# LPCB235_-_HEC5-8.net
KiCad netlist of a schematic drawn in Altium Designer
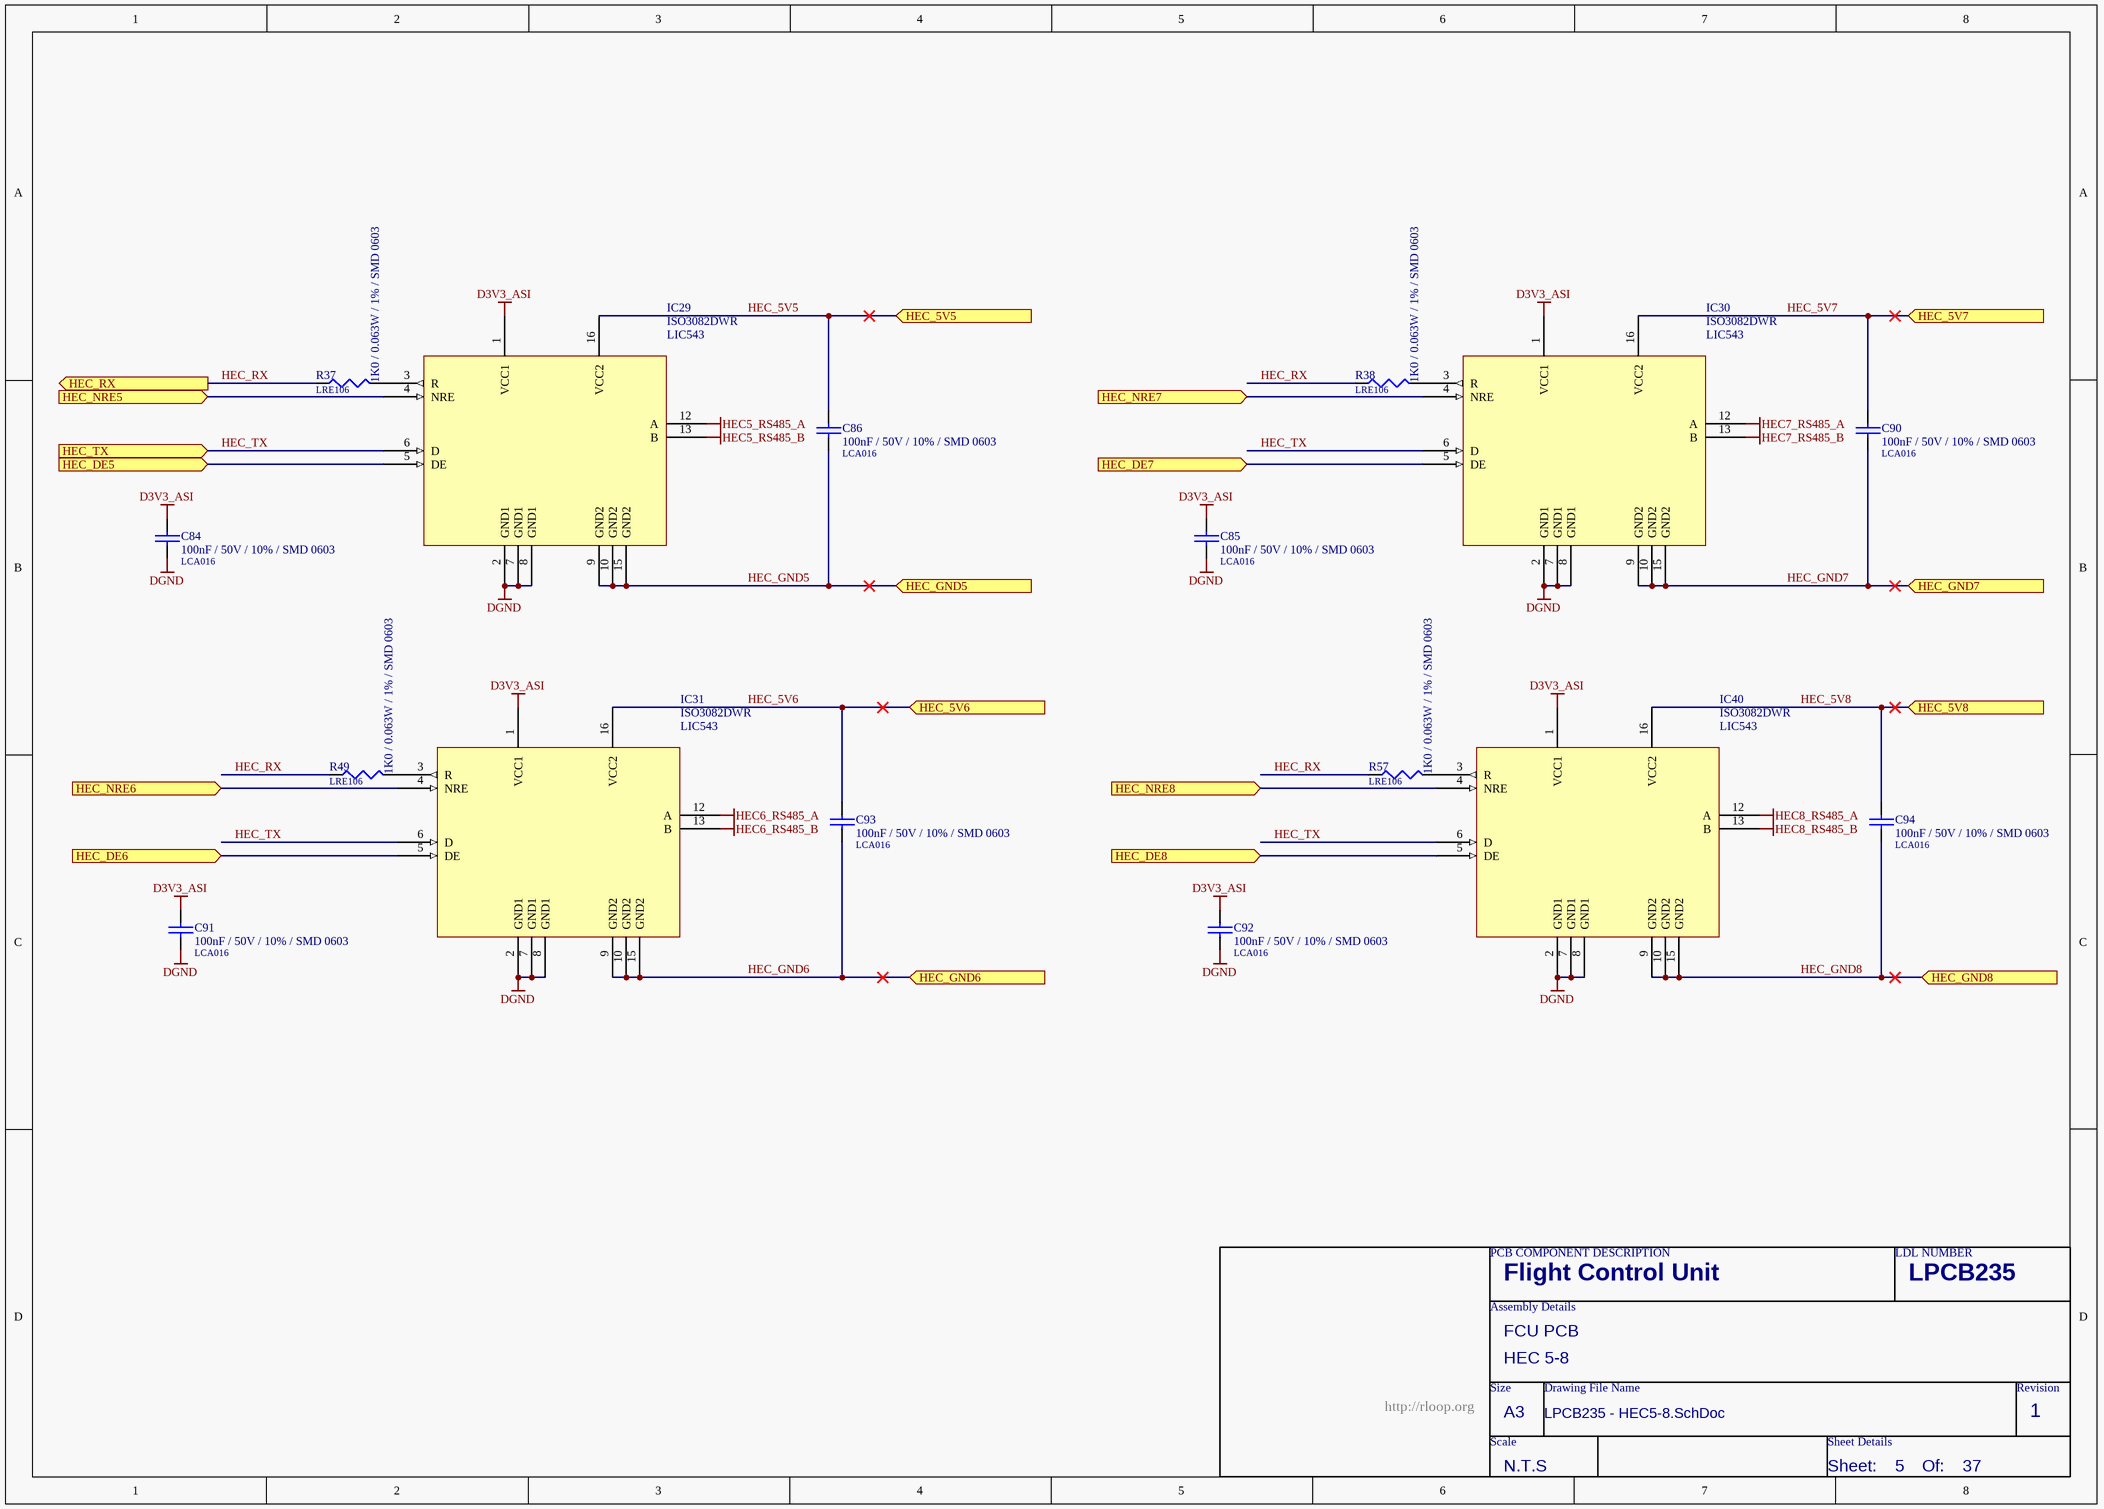
[diagram p0: LPCB235 - HEC5-8.SchDoc]

(export (version "E")
  (design (tool "Eeschema 10.0.6"))
  (components
    (comp (ref "C84")
      (value "100nF / 50V / 10% / SMD 0603")
      (footprint "LFP011__CC1608-0603-IPC7351_B")
      (description "Capacitor, Ceramic Chip, 100nF (0.1uF), 50V, 5%, SMD 0603 [LCA016]")
      (fields (field (name "LDL_NUMBER") "LCA016"))
      (libsource (lib "LDL_Capacitors") (part "100nF / 50V / 10% / SMD 0603"))
    )
    (comp (ref "C85")
      (value "100nF / 50V / 10% / SMD 0603")
      (footprint "LFP011__CC1608-0603-IPC7351_B")
      (description "Capacitor, Ceramic Chip, 100nF (0.1uF), 50V, 5%, SMD 0603 [LCA016]")
      (fields (field (name "LDL_NUMBER") "LCA016"))
      (libsource (lib "LDL_Capacitors") (part "100nF / 50V / 10% / SMD 0603"))
    )
    (comp (ref "C86")
      (value "100nF / 50V / 10% / SMD 0603")
      (footprint "LFP011__CC1608-0603-IPC7351_B")
      (description "Capacitor, Ceramic Chip, 100nF (0.1uF), 50V, 5%, SMD 0603 [LCA016]")
      (fields (field (name "LDL_NUMBER") "LCA016"))
      (libsource (lib "LDL_Capacitors") (part "100nF / 50V / 10% / SMD 0603"))
    )
    (comp (ref "C90")
      (value "100nF / 50V / 10% / SMD 0603")
      (footprint "LFP011__CC1608-0603-IPC7351_B")
      (description "Capacitor, Ceramic Chip, 100nF (0.1uF), 50V, 5%, SMD 0603 [LCA016]")
      (fields (field (name "LDL_NUMBER") "LCA016"))
      (libsource (lib "LDL_Capacitors") (part "100nF / 50V / 10% / SMD 0603"))
    )
    (comp (ref "C91")
      (value "100nF / 50V / 10% / SMD 0603")
      (footprint "LFP011__CC1608-0603-IPC7351_B")
      (description "Capacitor, Ceramic Chip, 100nF (0.1uF), 50V, 5%, SMD 0603 [LCA016]")
      (fields (field (name "LDL_NUMBER") "LCA016"))
      (libsource (lib "LDL_Capacitors") (part "100nF / 50V / 10% / SMD 0603"))
    )
    (comp (ref "C92")
      (value "100nF / 50V / 10% / SMD 0603")
      (footprint "LFP011__CC1608-0603-IPC7351_B")
      (description "Capacitor, Ceramic Chip, 100nF (0.1uF), 50V, 5%, SMD 0603 [LCA016]")
      (fields (field (name "LDL_NUMBER") "LCA016"))
      (libsource (lib "LDL_Capacitors") (part "100nF / 50V / 10% / SMD 0603"))
    )
    (comp (ref "C93")
      (value "100nF / 50V / 10% / SMD 0603")
      (footprint "LFP011__CC1608-0603-IPC7351_B")
      (description "Capacitor, Ceramic Chip, 100nF (0.1uF), 50V, 5%, SMD 0603 [LCA016]")
      (fields (field (name "LDL_NUMBER") "LCA016"))
      (libsource (lib "LDL_Capacitors") (part "100nF / 50V / 10% / SMD 0603"))
    )
    (comp (ref "C94")
      (value "100nF / 50V / 10% / SMD 0603")
      (footprint "LFP011__CC1608-0603-IPC7351_B")
      (description "Capacitor, Ceramic Chip, 100nF (0.1uF), 50V, 5%, SMD 0603 [LCA016]")
      (fields (field (name "LDL_NUMBER") "LCA016"))
      (libsource (lib "LDL_Capacitors") (part "100nF / 50V / 10% / SMD 0603"))
    )
    (comp (ref "IC29")
      (value "ISO3082DWR")
      (footprint "LFP068__SO-G16/G6.9")
      (description "IC, RS485 Isolator, SMD SOIC 16 [LIC543]")
      (fields (field (name "LDL_NUMBER") "LIC543"))
      (libsource (lib "LDL_Semiconductors") (part "ISO3082DWR"))
    )
    (comp (ref "IC30")
      (value "ISO3082DWR")
      (footprint "LFP068__SO-G16/G6.9")
      (description "IC, RS485 Isolator, SMD SOIC 16 [LIC543]")
      (fields (field (name "LDL_NUMBER") "LIC543"))
      (libsource (lib "LDL_Semiconductors") (part "ISO3082DWR"))
    )
    (comp (ref "IC31")
      (value "ISO3082DWR")
      (footprint "LFP068__SO-G16/G6.9")
      (description "IC, RS485 Isolator, SMD SOIC 16 [LIC543]")
      (fields (field (name "LDL_NUMBER") "LIC543"))
      (libsource (lib "LDL_Semiconductors") (part "ISO3082DWR"))
    )
    (comp (ref "IC40")
      (value "ISO3082DWR")
      (footprint "LFP068__SO-G16/G6.9")
      (description "IC, RS485 Isolator, SMD SOIC 16 [LIC543]")
      (fields (field (name "LDL_NUMBER") "LIC543"))
      (libsource (lib "LDL_Semiconductors") (part "ISO3082DWR"))
    )
    (comp (ref "R37")
      (value "1K0 / 0.063W / 1% / SMD 0603")
      (footprint "LFP020__CR1608-0603-IPC7351_B")
      (description "Resistor, Ceramic Chip, 1K0, 0.063W, 1%, SMD 0603 [LRE106]")
      (fields (field (name "LDL_NUMBER") "LRE106"))
      (libsource (lib "LDL_Resistors") (part "1K0 / 0.063W / 1% / SMD 0603"))
    )
    (comp (ref "R38")
      (value "1K0 / 0.063W / 1% / SMD 0603")
      (footprint "LFP020__CR1608-0603-IPC7351_B")
      (description "Resistor, Ceramic Chip, 1K0, 0.063W, 1%, SMD 0603 [LRE106]")
      (fields (field (name "LDL_NUMBER") "LRE106"))
      (libsource (lib "LDL_Resistors") (part "1K0 / 0.063W / 1% / SMD 0603"))
    )
    (comp (ref "R49")
      (value "1K0 / 0.063W / 1% / SMD 0603")
      (footprint "LFP020__CR1608-0603-IPC7351_B")
      (description "Resistor, Ceramic Chip, 1K0, 0.063W, 1%, SMD 0603 [LRE106]")
      (fields (field (name "LDL_NUMBER") "LRE106"))
      (libsource (lib "LDL_Resistors") (part "1K0 / 0.063W / 1% / SMD 0603"))
    )
    (comp (ref "R57")
      (value "1K0 / 0.063W / 1% / SMD 0603")
      (footprint "LFP020__CR1608-0603-IPC7351_B")
      (description "Resistor, Ceramic Chip, 1K0, 0.063W, 1%, SMD 0603 [LRE106]")
      (fields (field (name "LDL_NUMBER") "LRE106"))
      (libsource (lib "LDL_Resistors") (part "1K0 / 0.063W / 1% / SMD 0603"))
    )
  )
  (nets
    (net (code "1") (name "/HEC_5V5") (class "Default")
      (node (ref "C86") (pin "1") (pintype "passive"))
      (node (ref "IC29") (pin "16") (pinfunction "VCC2_16") (pintype "power_in"))
    )
    (net (code "2") (name "/HEC_5V6") (class "Default")
      (node (ref "C93") (pin "1") (pintype "passive"))
      (node (ref "IC31") (pin "16") (pinfunction "VCC2_16") (pintype "power_in"))
    )
    (net (code "3") (name "/HEC_5V7") (class "Default")
      (node (ref "C90") (pin "1") (pintype "passive"))
      (node (ref "IC30") (pin "16") (pinfunction "VCC2_16") (pintype "power_in"))
    )
    (net (code "4") (name "/HEC_5V8") (class "Default")
      (node (ref "C94") (pin "1") (pintype "passive"))
      (node (ref "IC40") (pin "16") (pinfunction "VCC2_16") (pintype "power_in"))
    )
    (net (code "5") (name "/HEC_DE5") (class "Default")
      (node (ref "IC29") (pin "5") (pinfunction "DE_5") (pintype "input"))
    )
    (net (code "6") (name "/HEC_DE6") (class "Default")
      (node (ref "IC31") (pin "5") (pinfunction "DE_5") (pintype "input"))
    )
    (net (code "7") (name "/HEC_DE7") (class "Default")
      (node (ref "IC30") (pin "5") (pinfunction "DE_5") (pintype "input"))
    )
    (net (code "8") (name "/HEC_DE8") (class "Default")
      (node (ref "IC40") (pin "5") (pinfunction "DE_5") (pintype "input"))
    )
    (net (code "9") (name "/HEC_GND5") (class "Default")
      (node (ref "C86") (pin "2") (pintype "passive"))
      (node (ref "IC29") (pin "10") (pinfunction "GND2_10") (pintype "power_in"))
      (node (ref "IC29") (pin "15") (pinfunction "GND2_15") (pintype "power_in"))
      (node (ref "IC29") (pin "9") (pinfunction "GND2_9") (pintype "power_in"))
    )
    (net (code "10") (name "/HEC_GND6") (class "Default")
      (node (ref "C93") (pin "2") (pintype "passive"))
      (node (ref "IC31") (pin "10") (pinfunction "GND2_10") (pintype "power_in"))
      (node (ref "IC31") (pin "15") (pinfunction "GND2_15") (pintype "power_in"))
      (node (ref "IC31") (pin "9") (pinfunction "GND2_9") (pintype "power_in"))
    )
    (net (code "11") (name "/HEC_GND7") (class "Default")
      (node (ref "C90") (pin "2") (pintype "passive"))
      (node (ref "IC30") (pin "10") (pinfunction "GND2_10") (pintype "power_in"))
      (node (ref "IC30") (pin "15") (pinfunction "GND2_15") (pintype "power_in"))
      (node (ref "IC30") (pin "9") (pinfunction "GND2_9") (pintype "power_in"))
    )
    (net (code "12") (name "/HEC_GND8") (class "Default")
      (node (ref "C94") (pin "2") (pintype "passive"))
      (node (ref "IC40") (pin "10") (pinfunction "GND2_10") (pintype "power_in"))
      (node (ref "IC40") (pin "15") (pinfunction "GND2_15") (pintype "power_in"))
      (node (ref "IC40") (pin "9") (pinfunction "GND2_9") (pintype "power_in"))
    )
    (net (code "13") (name "/HEC_NRE5") (class "Default")
      (node (ref "IC29") (pin "4") (pinfunction "NRE_4") (pintype "input"))
    )
    (net (code "14") (name "/HEC_NRE6") (class "Default")
      (node (ref "IC31") (pin "4") (pinfunction "NRE_4") (pintype "input"))
    )
    (net (code "15") (name "/HEC_NRE7") (class "Default")
      (node (ref "IC30") (pin "4") (pinfunction "NRE_4") (pintype "input"))
    )
    (net (code "16") (name "/HEC_NRE8") (class "Default")
      (node (ref "IC40") (pin "4") (pinfunction "NRE_4") (pintype "input"))
    )
    (net (code "17") (name "/HEC_RX") (class "Default")
      (node (ref "R37") (pin "1") (pintype "passive"))
      (node (ref "R38") (pin "1") (pintype "passive"))
      (node (ref "R49") (pin "1") (pintype "passive"))
      (node (ref "R57") (pin "1") (pintype "passive"))
    )
    (net (code "18") (name "/HEC_TX") (class "Default")
      (node (ref "IC29") (pin "6") (pinfunction "D_6") (pintype "input"))
      (node (ref "IC30") (pin "6") (pinfunction "D_6") (pintype "input"))
      (node (ref "IC31") (pin "6") (pinfunction "D_6") (pintype "input"))
      (node (ref "IC40") (pin "6") (pinfunction "D_6") (pintype "input"))
    )
    (net (code "19") (name "D3V3_ASI") (class "Default")
      (node (ref "C84") (pin "1") (pintype "passive"))
      (node (ref "C85") (pin "1") (pintype "passive"))
      (node (ref "C91") (pin "1") (pintype "passive"))
      (node (ref "C92") (pin "1") (pintype "passive"))
      (node (ref "IC29") (pin "1") (pinfunction "VCC1_1") (pintype "power_in"))
      (node (ref "IC30") (pin "1") (pinfunction "VCC1_1") (pintype "power_in"))
      (node (ref "IC31") (pin "1") (pinfunction "VCC1_1") (pintype "power_in"))
      (node (ref "IC40") (pin "1") (pinfunction "VCC1_1") (pintype "power_in"))
    )
    (net (code "20") (name "DGND") (class "Default")
      (node (ref "C84") (pin "2") (pintype "passive"))
      (node (ref "C85") (pin "2") (pintype "passive"))
      (node (ref "C91") (pin "2") (pintype "passive"))
      (node (ref "C92") (pin "2") (pintype "passive"))
      (node (ref "IC29") (pin "2") (pinfunction "GND1_2") (pintype "power_in"))
      (node (ref "IC29") (pin "7") (pinfunction "GND1_7") (pintype "power_in"))
      (node (ref "IC29") (pin "8") (pinfunction "GND1_8") (pintype "power_in"))
      (node (ref "IC30") (pin "2") (pinfunction "GND1_2") (pintype "power_in"))
      (node (ref "IC30") (pin "7") (pinfunction "GND1_7") (pintype "power_in"))
      (node (ref "IC30") (pin "8") (pinfunction "GND1_8") (pintype "power_in"))
      (node (ref "IC31") (pin "2") (pinfunction "GND1_2") (pintype "power_in"))
      (node (ref "IC31") (pin "7") (pinfunction "GND1_7") (pintype "power_in"))
      (node (ref "IC31") (pin "8") (pinfunction "GND1_8") (pintype "power_in"))
      (node (ref "IC40") (pin "2") (pinfunction "GND1_2") (pintype "power_in"))
      (node (ref "IC40") (pin "7") (pinfunction "GND1_7") (pintype "power_in"))
      (node (ref "IC40") (pin "8") (pinfunction "GND1_8") (pintype "power_in"))
    )
    (net (code "21") (name "HEC5_RS485_A") (class "Default")
      (node (ref "IC29") (pin "12") (pinfunction "A_12") (pintype "passive"))
    )
    (net (code "22") (name "HEC5_RS485_B") (class "Default")
      (node (ref "IC29") (pin "13") (pinfunction "B_13") (pintype "passive"))
    )
    (net (code "23") (name "HEC6_RS485_A") (class "Default")
      (node (ref "IC31") (pin "12") (pinfunction "A_12") (pintype "passive"))
    )
    (net (code "24") (name "HEC6_RS485_B") (class "Default")
      (node (ref "IC31") (pin "13") (pinfunction "B_13") (pintype "passive"))
    )
    (net (code "25") (name "HEC7_RS485_A") (class "Default")
      (node (ref "IC30") (pin "12") (pinfunction "A_12") (pintype "passive"))
    )
    (net (code "26") (name "HEC7_RS485_B") (class "Default")
      (node (ref "IC30") (pin "13") (pinfunction "B_13") (pintype "passive"))
    )
    (net (code "27") (name "HEC8_RS485_A") (class "Default")
      (node (ref "IC40") (pin "12") (pinfunction "A_12") (pintype "passive"))
    )
    (net (code "28") (name "HEC8_RS485_B") (class "Default")
      (node (ref "IC40") (pin "13") (pinfunction "B_13") (pintype "passive"))
    )
    (net (code "29") (name "Net-(IC29-R)") (class "Default")
      (node (ref "IC29") (pin "3") (pinfunction "R_3") (pintype "output"))
      (node (ref "R37") (pin "2") (pintype "passive"))
    )
    (net (code "30") (name "Net-(IC30-R)") (class "Default")
      (node (ref "IC30") (pin "3") (pinfunction "R_3") (pintype "output"))
      (node (ref "R38") (pin "2") (pintype "passive"))
    )
    (net (code "31") (name "Net-(IC31-R)") (class "Default")
      (node (ref "IC31") (pin "3") (pinfunction "R_3") (pintype "output"))
      (node (ref "R49") (pin "2") (pintype "passive"))
    )
    (net (code "32") (name "Net-(IC40-R)") (class "Default")
      (node (ref "IC40") (pin "3") (pinfunction "R_3") (pintype "output"))
      (node (ref "R57") (pin "2") (pintype "passive"))
    )
  )
)
